# fpga_core.net
KiCad netlist of a schematic drawn in Altium Designer
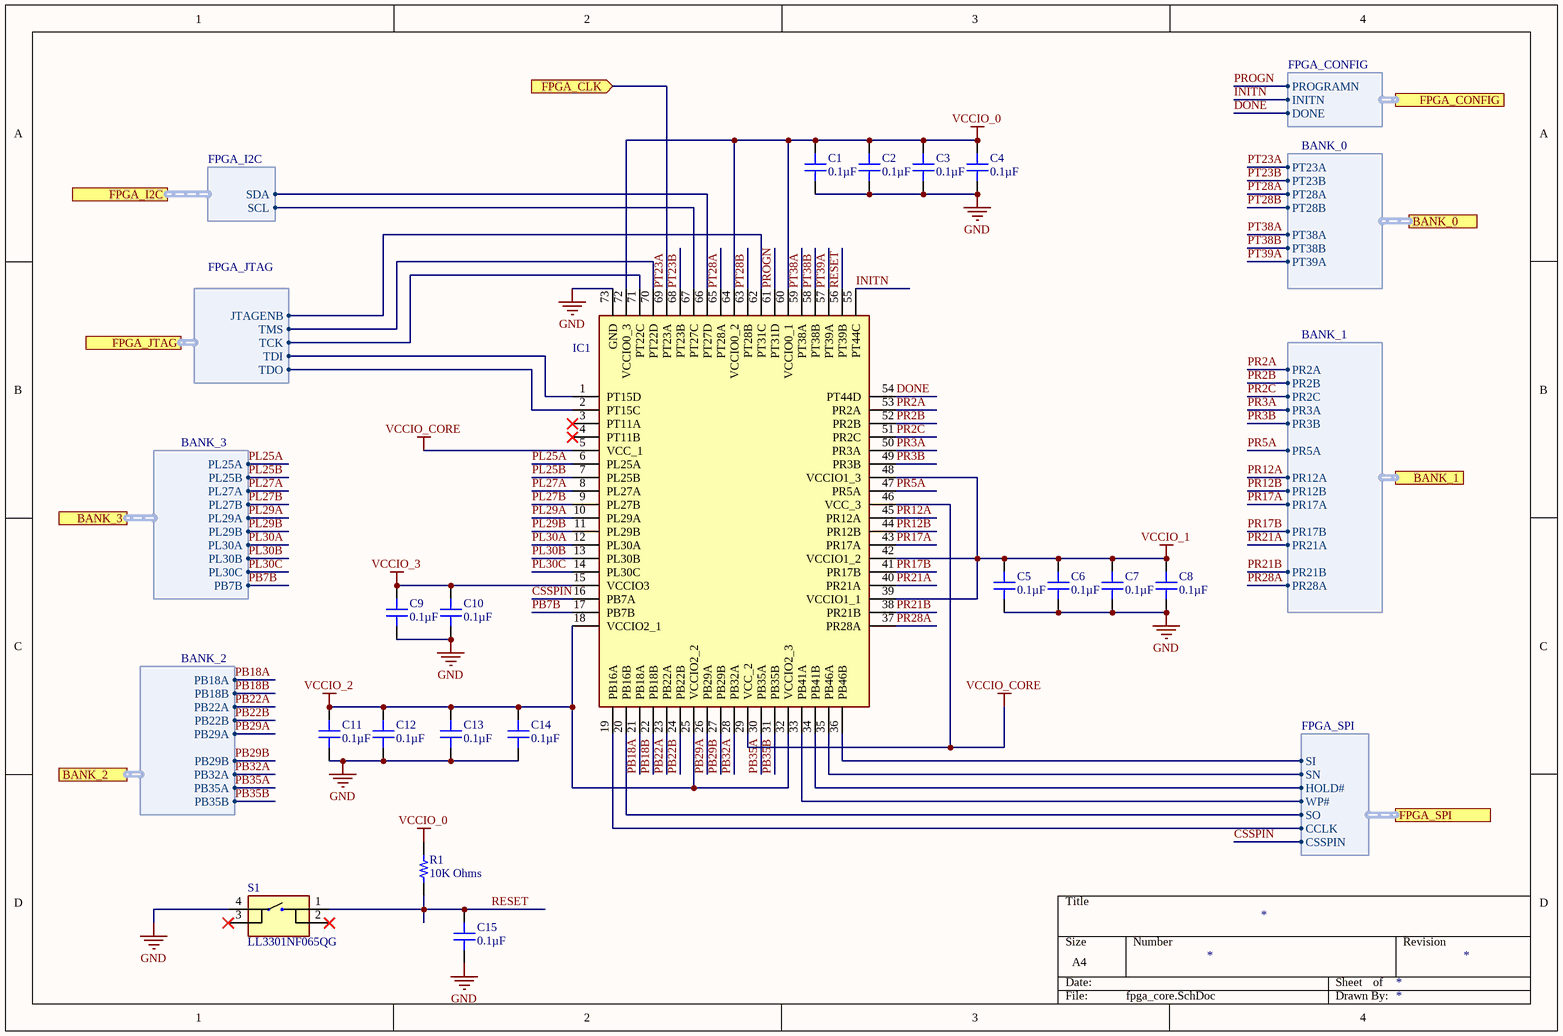
[diagram p0: fpga_core.SchDoc]

(export (version "E")
  (design (tool "Eeschema 10.0.6"))
  (components
    (comp (ref "C1")
      (value "0.1µF")
      (footprint "CAP 0603_1608")
      (description "CAP CER 0.1UF 16V X7R 0603")
      (fields (field (name "PART NUMBER") "CS0603KRX7R7BB104") (field (name "MANUFACTURER") "Yageo"))
      (libsource (lib "Celestial Altium Library - altium_library (2)") (part "Capacitor"))
    )
    (comp (ref "C2")
      (value "0.1µF")
      (footprint "CAP 0603_1608")
      (description "CAP CER 0.1UF 16V X7R 0603")
      (fields (field (name "PART NUMBER") "CS0603KRX7R7BB104") (field (name "MANUFACTURER") "Yageo"))
      (libsource (lib "Celestial Altium Library - altium_library (2)") (part "Capacitor"))
    )
    (comp (ref "C3")
      (value "0.1µF")
      (footprint "CAP 0603_1608")
      (description "CAP CER 0.1UF 16V X7R 0603")
      (fields (field (name "PART NUMBER") "CS0603KRX7R7BB104") (field (name "MANUFACTURER") "Yageo"))
      (libsource (lib "Celestial Altium Library - altium_library (2)") (part "Capacitor"))
    )
    (comp (ref "C4")
      (value "0.1µF")
      (footprint "CAP 0603_1608")
      (description "CAP CER 0.1UF 16V X7R 0603")
      (fields (field (name "PART NUMBER") "CS0603KRX7R7BB104") (field (name "MANUFACTURER") "Yageo"))
      (libsource (lib "Celestial Altium Library - altium_library (2)") (part "Capacitor"))
    )
    (comp (ref "C5")
      (value "0.1µF")
      (footprint "CAP 0603_1608")
      (description "CAP CER 0.1UF 16V X7R 0603")
      (fields (field (name "PART NUMBER") "CS0603KRX7R7BB104") (field (name "MANUFACTURER") "Yageo"))
      (libsource (lib "Celestial Altium Library - altium_library (2)") (part "Capacitor"))
    )
    (comp (ref "C6")
      (value "0.1µF")
      (footprint "CAP 0603_1608")
      (description "CAP CER 0.1UF 16V X7R 0603")
      (fields (field (name "PART NUMBER") "CS0603KRX7R7BB104") (field (name "MANUFACTURER") "Yageo"))
      (libsource (lib "Celestial Altium Library - altium_library (2)") (part "Capacitor"))
    )
    (comp (ref "C7")
      (value "0.1µF")
      (footprint "CAP 0603_1608")
      (description "CAP CER 0.1UF 16V X7R 0603")
      (fields (field (name "PART NUMBER") "CS0603KRX7R7BB104") (field (name "MANUFACTURER") "Yageo"))
      (libsource (lib "Celestial Altium Library - altium_library (2)") (part "Capacitor"))
    )
    (comp (ref "C8")
      (value "0.1µF")
      (footprint "CAP 0603_1608")
      (description "CAP CER 0.1UF 16V X7R 0603")
      (fields (field (name "PART NUMBER") "CS0603KRX7R7BB104") (field (name "MANUFACTURER") "Yageo"))
      (libsource (lib "Celestial Altium Library - altium_library (2)") (part "Capacitor"))
    )
    (comp (ref "C9")
      (value "0.1µF")
      (footprint "CAP 0603_1608")
      (description "CAP CER 0.1UF 16V X7R 0603")
      (fields (field (name "PART NUMBER") "CS0603KRX7R7BB104") (field (name "MANUFACTURER") "Yageo"))
      (libsource (lib "Celestial Altium Library - altium_library (2)") (part "Capacitor"))
    )
    (comp (ref "C10")
      (value "0.1µF")
      (footprint "CAP 0603_1608")
      (description "CAP CER 0.1UF 16V X7R 0603")
      (fields (field (name "PART NUMBER") "CS0603KRX7R7BB104") (field (name "MANUFACTURER") "Yageo"))
      (libsource (lib "Celestial Altium Library - altium_library (2)") (part "Capacitor"))
    )
    (comp (ref "C11")
      (value "0.1µF")
      (footprint "CAP 0603_1608")
      (description "CAP CER 0.1UF 16V X7R 0603")
      (fields (field (name "PART NUMBER") "CS0603KRX7R7BB104") (field (name "MANUFACTURER") "Yageo"))
      (libsource (lib "Celestial Altium Library - altium_library (2)") (part "Capacitor"))
    )
    (comp (ref "C12")
      (value "0.1µF")
      (footprint "CAP 0603_1608")
      (description "CAP CER 0.1UF 16V X7R 0603")
      (fields (field (name "PART NUMBER") "CS0603KRX7R7BB104") (field (name "MANUFACTURER") "Yageo"))
      (libsource (lib "Celestial Altium Library - altium_library (2)") (part "Capacitor"))
    )
    (comp (ref "C13")
      (value "0.1µF")
      (footprint "CAP 0603_1608")
      (description "CAP CER 0.1UF 16V X7R 0603")
      (fields (field (name "PART NUMBER") "CS0603KRX7R7BB104") (field (name "MANUFACTURER") "Yageo"))
      (libsource (lib "Celestial Altium Library - altium_library (2)") (part "Capacitor"))
    )
    (comp (ref "C14")
      (value "0.1µF")
      (footprint "CAP 0603_1608")
      (description "CAP CER 0.1UF 16V X7R 0603")
      (fields (field (name "PART NUMBER") "CS0603KRX7R7BB104") (field (name "MANUFACTURER") "Yageo"))
      (libsource (lib "Celestial Altium Library - altium_library (2)") (part "Capacitor"))
    )
    (comp (ref "C15")
      (value "0.1µF")
      (footprint "CAP 0603_1608")
      (description "CAP CER 0.1UF 16V X7R 0603")
      (fields (field (name "PART NUMBER") "CS0603KRX7R7BB104") (field (name "MANUFACTURER") "Yageo"))
      (libsource (lib "Celestial Altium Library - altium_library (2)") (part "Capacitor"))
    )
    (comp (ref "IC1")
      (value "LCMXO3D-9400HC-6SG72C")
      (footprint "SamacSys:QFN50P1000X1000X90-73N-D")
      (description "Integrated Circuit")
      (fields (field (name "MOUSER PART NUMBER") "842-O3D9400HC6SG72C"))
      (libsource (lib "SamacSys") (part "LCMXO3D-9400HC-6SG72C"))
    )
    (comp (ref "R1")
      (value "10K Ohms")
      (footprint "RES 0603_1608")
      (description "RES SMD 470 OHM 5% 1/4W 0603")
      (fields (field (name "PART NUMBER") "CRCW0603470RJNEAHP") (field (name "MANUFACTURER") "Vishay Dale"))
      (libsource (lib "Celestial Altium Library - altium_library (2)") (part "Resistor"))
    )
    (comp (ref "S1")
      (value "LL3301NF065QG")
      (footprint "SamacSys:LL3301NF065QG")
      (description "Switch")
      (fields (field (name "MOUSER PART NUMBER") "612-LL3301NF065QG"))
      (libsource (lib "SamacSys") (part "LL3301NF065QG"))
    )
  )
  (nets
    (net (code "9") (name "/CCLK") (class "Default")
      (node (ref "IC1") (pin "19") (pinfunction "PB16A_19") (pintype "passive"))
    )
    (net (code "10") (name "/CSSPIN") (class "Default")
      (node (ref "IC1") (pin "16") (pinfunction "PB7A_16") (pintype "passive"))
    )
    (net (code "11") (name "/DONE") (class "Default")
      (node (ref "IC1") (pin "54") (pinfunction "PT44D_54") (pintype "passive"))
    )
    (net (code "12") (name "/HOLD#") (class "Default")
      (node (ref "IC1") (pin "34") (pinfunction "PB41B_34") (pintype "passive"))
    )
    (net (code "13") (name "/INITN") (class "Default")
      (node (ref "IC1") (pin "55") (pinfunction "PT44C_55") (pintype "passive"))
    )
    (net (code "14") (name "/JTAGENB") (class "Default")
      (node (ref "IC1") (pin "62") (pinfunction "PT31C_62") (pintype "passive"))
    )
    (net (code "15") (name "/PB7B") (class "Default")
      (node (ref "IC1") (pin "17") (pinfunction "PB7B_17") (pintype "passive"))
    )
    (net (code "16") (name "/PB18A") (class "Default")
      (node (ref "IC1") (pin "21") (pinfunction "PB18A_21") (pintype "passive"))
    )
    (net (code "17") (name "/PB18B") (class "Default")
      (node (ref "IC1") (pin "22") (pinfunction "PB18B_22") (pintype "passive"))
    )
    (net (code "18") (name "/PB22A") (class "Default")
      (node (ref "IC1") (pin "23") (pinfunction "PB22A_23") (pintype "passive"))
    )
    (net (code "19") (name "/PB22B") (class "Default")
      (node (ref "IC1") (pin "24") (pinfunction "PB22B_24") (pintype "passive"))
    )
    (net (code "20") (name "/PB29A") (class "Default")
      (node (ref "IC1") (pin "26") (pinfunction "PB29A_26") (pintype "passive"))
    )
    (net (code "21") (name "/PB29B") (class "Default")
      (node (ref "IC1") (pin "27") (pinfunction "PB29B_27") (pintype "passive"))
    )
    (net (code "22") (name "/PB32A") (class "Default")
      (node (ref "IC1") (pin "28") (pinfunction "PB32A_28") (pintype "passive"))
    )
    (net (code "23") (name "/PB35A") (class "Default")
      (node (ref "IC1") (pin "30") (pinfunction "PB35A_30") (pintype "passive"))
    )
    (net (code "24") (name "/PB35B") (class "Default")
      (node (ref "IC1") (pin "31") (pinfunction "PB35B_31") (pintype "passive"))
    )
    (net (code "25") (name "/PL25A") (class "Default")
      (node (ref "IC1") (pin "6") (pinfunction "PL25A_6") (pintype "passive"))
    )
    (net (code "26") (name "/PL25B") (class "Default")
      (node (ref "IC1") (pin "7") (pinfunction "PL25B_7") (pintype "passive"))
    )
    (net (code "27") (name "/PL27A") (class "Default")
      (node (ref "IC1") (pin "8") (pinfunction "PL27A_8") (pintype "passive"))
    )
    (net (code "28") (name "/PL27B") (class "Default")
      (node (ref "IC1") (pin "9") (pinfunction "PL27B_9") (pintype "passive"))
    )
    (net (code "29") (name "/PL29A") (class "Default")
      (node (ref "IC1") (pin "10") (pinfunction "PL29A_10") (pintype "passive"))
    )
    (net (code "30") (name "/PL29B") (class "Default")
      (node (ref "IC1") (pin "11") (pinfunction "PL29B_11") (pintype "passive"))
    )
    (net (code "31") (name "/PL30A") (class "Default")
      (node (ref "IC1") (pin "12") (pinfunction "PL30A_12") (pintype "passive"))
    )
    (net (code "32") (name "/PL30B") (class "Default")
      (node (ref "IC1") (pin "13") (pinfunction "PL30B_13") (pintype "passive"))
    )
    (net (code "33") (name "/PL30C") (class "Default")
      (node (ref "IC1") (pin "14") (pinfunction "PL30C_14") (pintype "passive"))
    )
    (net (code "34") (name "/PR2A") (class "Default")
      (node (ref "IC1") (pin "53") (pinfunction "PR2A_53") (pintype "passive"))
    )
    (net (code "35") (name "/PR2B") (class "Default")
      (node (ref "IC1") (pin "52") (pinfunction "PR2B_52") (pintype "passive"))
    )
    (net (code "36") (name "/PR2C") (class "Default")
      (node (ref "IC1") (pin "51") (pinfunction "PR2C_51") (pintype "passive"))
    )
    (net (code "37") (name "/PR3A") (class "Default")
      (node (ref "IC1") (pin "50") (pinfunction "PR3A_50") (pintype "passive"))
    )
    (net (code "38") (name "/PR3B") (class "Default")
      (node (ref "IC1") (pin "49") (pinfunction "PR3B_49") (pintype "passive"))
    )
    (net (code "39") (name "/PR5A") (class "Default")
      (node (ref "IC1") (pin "47") (pinfunction "PR5A_47") (pintype "passive"))
    )
    (net (code "40") (name "/PR12A") (class "Default")
      (node (ref "IC1") (pin "45") (pinfunction "PR12A_45") (pintype "passive"))
    )
    (net (code "41") (name "/PR12B") (class "Default")
      (node (ref "IC1") (pin "44") (pinfunction "PR12B_44") (pintype "passive"))
    )
    (net (code "42") (name "/PR17A") (class "Default")
      (node (ref "IC1") (pin "43") (pinfunction "PR17A_43") (pintype "passive"))
    )
    (net (code "43") (name "/PR17B") (class "Default")
      (node (ref "IC1") (pin "41") (pinfunction "PR17B_41") (pintype "passive"))
    )
    (net (code "44") (name "/PR21A") (class "Default")
      (node (ref "IC1") (pin "40") (pinfunction "PR21A_40") (pintype "passive"))
    )
    (net (code "45") (name "/PR21B") (class "Default")
      (node (ref "IC1") (pin "38") (pinfunction "PR21B_38") (pintype "passive"))
    )
    (net (code "46") (name "/PR28A") (class "Default")
      (node (ref "IC1") (pin "37") (pinfunction "PR28A_37") (pintype "passive"))
    )
    (net (code "47") (name "/PROGN") (class "Default")
      (node (ref "IC1") (pin "61") (pinfunction "PT31D_61") (pintype "passive"))
    )
    (net (code "48") (name "/PT23A") (class "Default")
      (node (ref "IC1") (pin "69") (pinfunction "PT23A_69") (pintype "passive"))
    )
    (net (code "49") (name "/PT23B") (class "Default")
      (node (ref "IC1") (pin "68") (pinfunction "PT23B_68") (pintype "passive"))
    )
    (net (code "50") (name "/PT28A") (class "Default")
      (node (ref "IC1") (pin "65") (pinfunction "PT28A_65") (pintype "passive"))
    )
    (net (code "51") (name "/PT28B") (class "Default")
      (node (ref "IC1") (pin "63") (pinfunction "PT28B_63") (pintype "passive"))
    )
    (net (code "52") (name "/PT38A") (class "Default")
      (node (ref "IC1") (pin "59") (pinfunction "PT38A_59") (pintype "passive"))
    )
    (net (code "53") (name "/PT38B") (class "Default")
      (node (ref "IC1") (pin "58") (pinfunction "PT38B_58") (pintype "passive"))
    )
    (net (code "54") (name "/PT39A") (class "Default")
      (node (ref "IC1") (pin "57") (pinfunction "PT39A_57") (pintype "passive"))
    )
    (net (code "55") (name "/RESET") (class "Default")
      (node (ref "C15") (pin "2") (pinfunction "2_2") (pintype "passive"))
      (node (ref "IC1") (pin "56") (pinfunction "PT39B_56") (pintype "passive"))
      (node (ref "R1") (pin "1") (pinfunction "1_1") (pintype "passive"))
      (node (ref "S1") (pin "1") (pinfunction "1_1") (pintype "passive"))
    )
    (net (code "56") (name "/SCL") (class "Default")
      (node (ref "IC1") (pin "67") (pinfunction "PT27C_67") (pintype "passive"))
    )
    (net (code "57") (name "/SDA") (class "Default")
      (node (ref "IC1") (pin "66") (pinfunction "PT27D_66") (pintype "passive"))
    )
    (net (code "58") (name "/SI") (class "Default")
      (node (ref "IC1") (pin "36") (pinfunction "PB46B_36") (pintype "passive"))
    )
    (net (code "59") (name "/SN") (class "Default")
      (node (ref "IC1") (pin "35") (pinfunction "PB46A_35") (pintype "passive"))
    )
    (net (code "60") (name "/SO") (class "Default")
      (node (ref "IC1") (pin "20") (pinfunction "PB16B_20") (pintype "passive"))
    )
    (net (code "61") (name "/TCK") (class "Default")
      (node (ref "IC1") (pin "71") (pinfunction "PT22C_71") (pintype "passive"))
    )
    (net (code "62") (name "/TDI") (class "Default")
      (node (ref "IC1") (pin "1") (pinfunction "PT15D_1") (pintype "passive"))
    )
    (net (code "63") (name "/TDO") (class "Default")
      (node (ref "IC1") (pin "2") (pinfunction "PT15C_2") (pintype "passive"))
    )
    (net (code "64") (name "/TMS") (class "Default")
      (node (ref "IC1") (pin "70") (pinfunction "PT22D_70") (pintype "passive"))
    )
    (net (code "65") (name "/WP#") (class "Default")
      (node (ref "IC1") (pin "33") (pinfunction "PB41A_33") (pintype "passive"))
    )
    (net (code "74") (name "GND") (class "Default")
      (node (ref "C1") (pin "1") (pinfunction "1_1") (pintype "passive"))
      (node (ref "C10") (pin "1") (pinfunction "1_1") (pintype "passive"))
      (node (ref "C11") (pin "1") (pinfunction "1_1") (pintype "passive"))
      (node (ref "C12") (pin "1") (pinfunction "1_1") (pintype "passive"))
      (node (ref "C13") (pin "1") (pinfunction "1_1") (pintype "passive"))
      (node (ref "C14") (pin "1") (pinfunction "1_1") (pintype "passive"))
      (node (ref "C15") (pin "1") (pinfunction "1_1") (pintype "passive"))
      (node (ref "C2") (pin "1") (pinfunction "1_1") (pintype "passive"))
      (node (ref "C3") (pin "1") (pinfunction "1_1") (pintype "passive"))
      (node (ref "C4") (pin "1") (pinfunction "1_1") (pintype "passive"))
      (node (ref "C5") (pin "1") (pinfunction "1_1") (pintype "passive"))
      (node (ref "C6") (pin "1") (pinfunction "1_1") (pintype "passive"))
      (node (ref "C7") (pin "1") (pinfunction "1_1") (pintype "passive"))
      (node (ref "C8") (pin "1") (pinfunction "1_1") (pintype "passive"))
      (node (ref "C9") (pin "1") (pinfunction "1_1") (pintype "passive"))
      (node (ref "IC1") (pin "73") (pinfunction "GND_73") (pintype "passive"))
      (node (ref "S1") (pin "4") (pinfunction "4_4") (pintype "passive"))
    )
    (net (code "75") (name "VCCIO_0") (class "Default")
      (node (ref "C1") (pin "2") (pinfunction "2_2") (pintype "passive"))
      (node (ref "C2") (pin "2") (pinfunction "2_2") (pintype "passive"))
      (node (ref "C3") (pin "2") (pinfunction "2_2") (pintype "passive"))
      (node (ref "C4") (pin "2") (pinfunction "2_2") (pintype "passive"))
      (node (ref "IC1") (pin "60") (pinfunction "VCCIO0_1_60") (pintype "passive"))
      (node (ref "IC1") (pin "64") (pinfunction "VCCIO0_2_64") (pintype "passive"))
      (node (ref "IC1") (pin "72") (pinfunction "VCCIO0_3_72") (pintype "passive"))
      (node (ref "R1") (pin "2") (pinfunction "2_2") (pintype "passive"))
    )
    (net (code "76") (name "VCCIO_1") (class "Default")
      (node (ref "C5") (pin "2") (pinfunction "2_2") (pintype "passive"))
      (node (ref "C6") (pin "2") (pinfunction "2_2") (pintype "passive"))
      (node (ref "C7") (pin "2") (pinfunction "2_2") (pintype "passive"))
      (node (ref "C8") (pin "2") (pinfunction "2_2") (pintype "passive"))
      (node (ref "IC1") (pin "39") (pinfunction "VCCIO1_1_39") (pintype "passive"))
      (node (ref "IC1") (pin "42") (pinfunction "VCCIO1_2_42") (pintype "passive"))
      (node (ref "IC1") (pin "48") (pinfunction "VCCIO1_3_48") (pintype "passive"))
    )
    (net (code "77") (name "VCCIO_2") (class "Default")
      (node (ref "C11") (pin "2") (pinfunction "2_2") (pintype "passive"))
      (node (ref "C12") (pin "2") (pinfunction "2_2") (pintype "passive"))
      (node (ref "C13") (pin "2") (pinfunction "2_2") (pintype "passive"))
      (node (ref "C14") (pin "2") (pinfunction "2_2") (pintype "passive"))
      (node (ref "IC1") (pin "18") (pinfunction "VCCIO2_1_18") (pintype "passive"))
      (node (ref "IC1") (pin "25") (pinfunction "VCCIO2_2_25") (pintype "passive"))
      (node (ref "IC1") (pin "32") (pinfunction "VCCIO2_3_32") (pintype "passive"))
    )
    (net (code "78") (name "VCCIO_3") (class "Default")
      (node (ref "C10") (pin "2") (pinfunction "2_2") (pintype "passive"))
      (node (ref "C9") (pin "2") (pinfunction "2_2") (pintype "passive"))
      (node (ref "IC1") (pin "15") (pinfunction "VCCIO3_15") (pintype "passive"))
    )
    (net (code "79") (name "VCCIO_CORE") (class "Default")
      (node (ref "IC1") (pin "29") (pinfunction "VCC_2_29") (pintype "passive"))
      (node (ref "IC1") (pin "46") (pinfunction "VCC_3_46") (pintype "passive"))
      (node (ref "IC1") (pin "5") (pinfunction "VCC_1_5") (pintype "passive"))
    )
    (net (code "80") (name "unconnected-(IC1-PT11A-Pad3)") (class "Default")
      (node (ref "IC1") (pin "3") (pinfunction "PT11A_3") (pintype "passive+no_connect"))
    )
    (net (code "81") (name "unconnected-(IC1-PT11B-Pad4)") (class "Default")
      (node (ref "IC1") (pin "4") (pinfunction "PT11B_4") (pintype "passive+no_connect"))
    )
    (net (code "82") (name "unconnected-(S1-Pad2)") (class "Default")
      (node (ref "S1") (pin "2") (pinfunction "2_2") (pintype "passive+no_connect"))
    )
    (net (code "83") (name "unconnected-(S1-Pad3)") (class "Default")
      (node (ref "S1") (pin "3") (pinfunction "3_3") (pintype "passive+no_connect"))
    )
  )
)
